# v0.net
KiCad netlist of a schematic drawn in Altium Designer
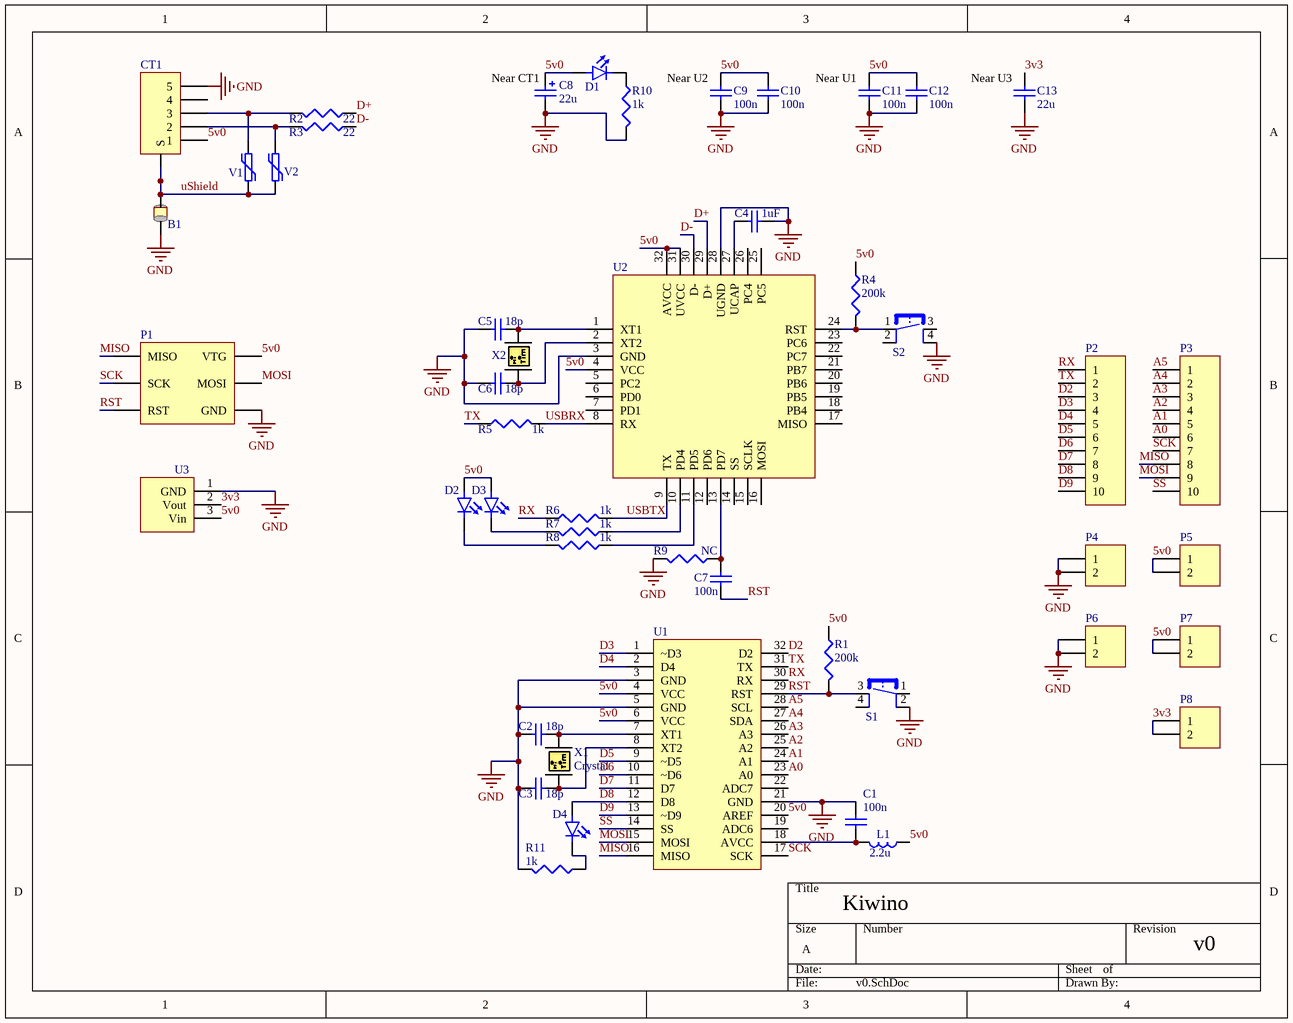
[diagram p0: v0.SchDoc]

(export (version "E")
  (design (tool "Eeschema 10.0.6"))
  (components
    (comp (ref "B1")
      (value "Ferrite Bead")
      (footprint "smd0603")
      (libsource (lib "Components") (part "Ferrite Bead"))
    )
    (comp (ref "C1")
      (value "100n")
      (footprint "SMD0603_cap")
      (description "Ceramic Chip Capacitor")
      (fields (field (name "Comment") "Cap"))
      (libsource (lib "Components") (part "Capacitor Ceramic"))
    )
    (comp (ref "C2")
      (value "18p")
      (footprint "SMD0603_cap")
      (description "Ceramic Chip Capacitor")
      (fields (field (name "Comment") "Cap"))
      (libsource (lib "Components") (part "Capacitor Ceramic"))
    )
    (comp (ref "C3")
      (value "18p")
      (footprint "SMD0603_cap")
      (description "Ceramic Chip Capacitor")
      (fields (field (name "Comment") "Cap"))
      (libsource (lib "Components") (part "Capacitor Ceramic"))
    )
    (comp (ref "C4")
      (value "1uF")
      (footprint "SMD0603_cap")
      (description "Ceramic Chip Capacitor")
      (fields (field (name "Comment") "Cap"))
      (libsource (lib "Components") (part "Capacitor Ceramic"))
    )
    (comp (ref "C5")
      (value "18p")
      (footprint "SMD0603_cap")
      (description "Ceramic Chip Capacitor")
      (fields (field (name "Comment") "Cap"))
      (libsource (lib "Components") (part "Capacitor Ceramic"))
    )
    (comp (ref "C6")
      (value "18p")
      (footprint "SMD0603_cap")
      (description "Ceramic Chip Capacitor")
      (fields (field (name "Comment") "Cap"))
      (libsource (lib "Components") (part "Capacitor Ceramic"))
    )
    (comp (ref "C7")
      (value "100n")
      (footprint "SMD0603_cap")
      (description "Ceramic Chip Capacitor")
      (fields (field (name "Comment") "Cap"))
      (libsource (lib "Components") (part "Capacitor Ceramic"))
    )
    (comp (ref "C8")
      (value "22u")
      (footprint "cap_radial_b")
      (description "Polarized Capacitor (Surface Mount)")
      (fields (field (name "Comment") "Cap"))
      (libsource (lib "Components") (part "Capacitor Polarized"))
    )
    (comp (ref "C9")
      (value "100n")
      (footprint "SMD0603_cap")
      (description "Ceramic Chip Capacitor")
      (fields (field (name "Comment") "Cap"))
      (libsource (lib "Components") (part "Capacitor Ceramic"))
    )
    (comp (ref "C10")
      (value "100n")
      (footprint "SMD0603_cap")
      (description "Ceramic Chip Capacitor")
      (fields (field (name "Comment") "Cap"))
      (libsource (lib "Components") (part "Capacitor Ceramic"))
    )
    (comp (ref "C11")
      (value "100n")
      (footprint "SMD0603_cap")
      (description "Ceramic Chip Capacitor")
      (fields (field (name "Comment") "Cap"))
      (libsource (lib "Components") (part "Capacitor Ceramic"))
    )
    (comp (ref "C12")
      (value "100n")
      (footprint "SMD0603_cap")
      (description "Ceramic Chip Capacitor")
      (fields (field (name "Comment") "Cap"))
      (libsource (lib "Components") (part "Capacitor Ceramic"))
    )
    (comp (ref "C13")
      (value "22u")
      (footprint "SMD0603_cap")
      (description "Ceramic Chip Capacitor")
      (fields (field (name "Comment") "Cap"))
      (libsource (lib "Components") (part "Capacitor Ceramic"))
    )
    (comp (ref "CT1")
      (value "Header")
      (footprint "microusb_2")
      (description "Micro USB")
      (libsource (lib "Components") (part "MICROUSB"))
    )
    (comp (ref "D1")
      (value "LED")
      (footprint "SMD0603 POLARIZED")
      (libsource (lib "Components") (part "LED"))
    )
    (comp (ref "D2")
      (value "LED")
      (footprint "SMD0603 POLARIZED")
      (libsource (lib "Components") (part "LED"))
    )
    (comp (ref "D3")
      (value "LED")
      (footprint "SMD0603 POLARIZED")
      (libsource (lib "Components") (part "LED"))
    )
    (comp (ref "D4")
      (value "LED")
      (footprint "SMD0603 POLARIZED")
      (libsource (lib "Components") (part "LED"))
    )
    (comp (ref "L1")
      (value "2.2u")
      (footprint "SMD0805")
      (description "Inductor")
      (fields (field (name "PUBLISHER") "Altium Limited"))
      (libsource (lib "Components") (part "Inductor"))
    )
    (comp (ref "P1")
      (value "ICSP Header")
      (footprint "Header 2x3")
      (libsource (lib "Components") (part "ICSP Header"))
    )
    (comp (ref "P2")
      (value "Header 10x1")
      (footprint "header 10x1")
      (libsource (lib "Components") (part "Header 10x1"))
    )
    (comp (ref "P3")
      (value "Header 10x1")
      (footprint "header 10x1")
      (libsource (lib "Components") (part "Header 10x1"))
    )
    (comp (ref "P4")
      (value "Header")
      (footprint "Header 2x1")
      (description "Header, 2-Pin")
      (libsource (lib "Components") (part "Header 2x1"))
    )
    (comp (ref "P5")
      (value "Header")
      (footprint "Header 2x1")
      (description "Header, 2-Pin")
      (libsource (lib "Components") (part "Header 2x1"))
    )
    (comp (ref "P6")
      (value "Header")
      (footprint "Header 2x1")
      (description "Header, 2-Pin")
      (libsource (lib "Components") (part "Header 2x1"))
    )
    (comp (ref "P7")
      (value "Header")
      (footprint "Header 2x1")
      (description "Header, 2-Pin")
      (libsource (lib "Components") (part "Header 2x1"))
    )
    (comp (ref "P8")
      (value "Header")
      (footprint "Header 2x1")
      (description "Header, 2-Pin")
      (libsource (lib "Components") (part "Header 2x1"))
    )
    (comp (ref "R1")
      (value "200k")
      (footprint "SMD0603")
      (description "Resistor")
      (fields (field (name "Comment") "Res"))
      (libsource (lib "Components") (part "Resistor"))
    )
    (comp (ref "R2")
      (value "22")
      (footprint "SMD0603")
      (description "Resistor")
      (fields (field (name "Comment") "Res"))
      (libsource (lib "Components") (part "Resistor"))
    )
    (comp (ref "R3")
      (value "22")
      (footprint "SMD0603")
      (description "Resistor")
      (fields (field (name "Comment") "Res"))
      (libsource (lib "Components") (part "Resistor"))
    )
    (comp (ref "R4")
      (value "200k")
      (footprint "SMD0603")
      (description "Resistor")
      (fields (field (name "Comment") "Res"))
      (libsource (lib "Components") (part "Resistor"))
    )
    (comp (ref "R5")
      (value "1k")
      (footprint "SMD0603")
      (description "Resistor")
      (fields (field (name "Comment") "Res"))
      (libsource (lib "Components") (part "Resistor"))
    )
    (comp (ref "R6")
      (value "1k")
      (footprint "SMD0603")
      (description "Resistor")
      (fields (field (name "Comment") "Res"))
      (libsource (lib "Components") (part "Resistor"))
    )
    (comp (ref "R7")
      (value "1k")
      (footprint "SMD0603")
      (description "Resistor")
      (fields (field (name "Comment") "Res"))
      (libsource (lib "Components") (part "Resistor"))
    )
    (comp (ref "R8")
      (value "1k")
      (footprint "SMD0603")
      (description "Resistor")
      (fields (field (name "Comment") "Res"))
      (libsource (lib "Components") (part "Resistor"))
    )
    (comp (ref "R9")
      (value "NC")
      (footprint "SMD0603")
      (description "Resistor")
      (fields (field (name "Comment") "Res"))
      (libsource (lib "Components") (part "Resistor"))
    )
    (comp (ref "R10")
      (value "1k")
      (footprint "SMD0603")
      (description "Resistor")
      (fields (field (name "Comment") "Res"))
      (libsource (lib "Components") (part "Resistor"))
    )
    (comp (ref "R11")
      (value "1k")
      (footprint "SMD0603")
      (description "Resistor")
      (fields (field (name "Comment") "Res"))
      (libsource (lib "Components") (part "Resistor"))
    )
    (comp (ref "S1")
      (value "Pushbutton")
      (footprint "pushbutton_smd")
      (libsource (lib "Components") (part "Pushbutton"))
    )
    (comp (ref "S2")
      (value "Pushbutton")
      (footprint "pushbutton_smd")
      (libsource (lib "Components") (part "Pushbutton"))
    )
    (comp (ref "U1")
      (value "ATMega328P_SMD")
      (footprint "tqfp-32")
      (libsource (lib "Components") (part "ATMega328P_SMD"))
    )
    (comp (ref "U2")
      (value "ATMega16U2")
      (footprint "tqfp-32")
      (libsource (lib "Components") (part "ATMega16U2"))
    )
    (comp (ref "U3")
      (value "AZ1117CH")
      (footprint "sot-223")
      (libsource (lib "Components") (part "AZ1117CH"))
    )
    (comp (ref "V1")
      (value "Varistor")
      (footprint "smd0603")
      (libsource (lib "Components") (part "Varistor"))
    )
    (comp (ref "V2")
      (value "Varistor")
      (footprint "smd0603")
      (libsource (lib "Components") (part "Varistor"))
    )
    (comp (ref "X1")
      (value "Crystal")
      (footprint "crystal_smd_2pin")
      (libsource (lib "Components") (part "Crystal"))
    )
    (comp (ref "X2")
      (value "Crystal")
      (footprint "crystal_smd_2pin")
      (libsource (lib "Components") (part "Crystal"))
    )
  )
  (nets
    (net (code "1") (name "/3v3") (class "Default")
      (node (ref "C13") (pin "1") (pinfunction "1_1") (pintype "passive"))
      (node (ref "P8") (pin "1") (pinfunction "1_1") (pintype "passive"))
      (node (ref "P8") (pin "2") (pinfunction "2_2") (pintype "passive"))
      (node (ref "U3") (pin "2") (pinfunction "Vout_2") (pintype "passive"))
    )
    (net (code "2") (name "/5v0") (class "Default")
      (node (ref "C10") (pin "1") (pinfunction "1_1") (pintype "passive"))
      (node (ref "C11") (pin "1") (pinfunction "1_1") (pintype "passive"))
      (node (ref "C12") (pin "1") (pinfunction "1_1") (pintype "passive"))
      (node (ref "C8") (pin "1") (pinfunction "1_1") (pintype "passive"))
      (node (ref "C9") (pin "1") (pinfunction "1_1") (pintype "passive"))
      (node (ref "CT1") (pin "1") (pinfunction "1_1") (pintype "passive"))
      (node (ref "D1") (pin "1") (pinfunction "Anode_(+)_1") (pintype "passive"))
      (node (ref "D2") (pin "1") (pinfunction "Anode_(+)_1") (pintype "passive"))
      (node (ref "D3") (pin "1") (pinfunction "Anode_(+)_1") (pintype "passive"))
      (node (ref "L1") (pin "1") (pinfunction "Source_1") (pintype "passive"))
      (node (ref "P1") (pin "2") (pinfunction "VTG_2") (pintype "passive"))
      (node (ref "P5") (pin "1") (pinfunction "1_1") (pintype "passive"))
      (node (ref "P5") (pin "2") (pinfunction "2_2") (pintype "passive"))
      (node (ref "P7") (pin "1") (pinfunction "1_1") (pintype "passive"))
      (node (ref "P7") (pin "2") (pinfunction "2_2") (pintype "passive"))
      (node (ref "R1") (pin "2") (pinfunction "2_2") (pintype "passive"))
      (node (ref "R4") (pin "2") (pinfunction "2_2") (pintype "passive"))
      (node (ref "U1") (pin "20") (pinfunction "AREF_20") (pintype "passive"))
      (node (ref "U1") (pin "4") (pinfunction "VCC_4") (pintype "passive"))
      (node (ref "U1") (pin "6") (pinfunction "VCC_6") (pintype "passive"))
      (node (ref "U2") (pin "31") (pinfunction "UVCC_31") (pintype "passive"))
      (node (ref "U2") (pin "32") (pinfunction "AVCC_32") (pintype "passive"))
      (node (ref "U2") (pin "4") (pinfunction "VCC_4") (pintype "passive"))
      (node (ref "U3") (pin "3") (pinfunction "Vin_3") (pintype "passive"))
    )
    (net (code "3") (name "/A0") (class "Default")
      (node (ref "P3") (pin "6") (pinfunction "6_6") (pintype "passive"))
      (node (ref "U1") (pin "23") (pinfunction "A0_23") (pintype "passive"))
    )
    (net (code "4") (name "/A1") (class "Default")
      (node (ref "P3") (pin "5") (pinfunction "5_5") (pintype "passive"))
      (node (ref "U1") (pin "24") (pinfunction "A1_24") (pintype "passive"))
    )
    (net (code "5") (name "/A2") (class "Default")
      (node (ref "P3") (pin "4") (pinfunction "4_4") (pintype "passive"))
      (node (ref "U1") (pin "25") (pinfunction "A2_25") (pintype "passive"))
    )
    (net (code "6") (name "/A3") (class "Default")
      (node (ref "P3") (pin "3") (pinfunction "3_3") (pintype "passive"))
      (node (ref "U1") (pin "26") (pinfunction "A3_26") (pintype "passive"))
    )
    (net (code "7") (name "/A4") (class "Default")
      (node (ref "P3") (pin "2") (pinfunction "2_2") (pintype "passive"))
      (node (ref "U1") (pin "27") (pinfunction "SDA_27") (pintype "passive"))
    )
    (net (code "8") (name "/A5") (class "Default")
      (node (ref "P3") (pin "1") (pinfunction "1_1") (pintype "passive"))
      (node (ref "U1") (pin "28") (pinfunction "SCL_28") (pintype "passive"))
    )
    (net (code "9") (name "/D+") (class "Default")
      (node (ref "R2") (pin "1") (pinfunction "1_1") (pintype "passive"))
      (node (ref "U2") (pin "29") (pinfunction "D+_29") (pintype "passive"))
    )
    (net (code "10") (name "/D-") (class "Default")
      (node (ref "R3") (pin "1") (pinfunction "1_1") (pintype "passive"))
      (node (ref "U2") (pin "30") (pinfunction "D-_30") (pintype "passive"))
    )
    (net (code "11") (name "/D2") (class "Default")
      (node (ref "P2") (pin "3") (pinfunction "3_3") (pintype "passive"))
      (node (ref "U1") (pin "32") (pinfunction "D2_32") (pintype "passive"))
    )
    (net (code "12") (name "/D3") (class "Default")
      (node (ref "P2") (pin "4") (pinfunction "4_4") (pintype "passive"))
      (node (ref "U1") (pin "1") (pinfunction "~D3_1") (pintype "passive"))
    )
    (net (code "13") (name "/D4") (class "Default")
      (node (ref "P2") (pin "5") (pinfunction "5_5") (pintype "passive"))
      (node (ref "U1") (pin "2") (pinfunction "D4_2") (pintype "passive"))
    )
    (net (code "14") (name "/D5") (class "Default")
      (node (ref "P2") (pin "6") (pinfunction "6_6") (pintype "passive"))
      (node (ref "U1") (pin "9") (pinfunction "~D5_9") (pintype "passive"))
    )
    (net (code "15") (name "/D6") (class "Default")
      (node (ref "P2") (pin "7") (pinfunction "7_7") (pintype "passive"))
      (node (ref "U1") (pin "10") (pinfunction "~D6_10") (pintype "passive"))
    )
    (net (code "16") (name "/D7") (class "Default")
      (node (ref "P2") (pin "8") (pinfunction "8_8") (pintype "passive"))
      (node (ref "U1") (pin "11") (pinfunction "D7_11") (pintype "passive"))
    )
    (net (code "17") (name "/D8") (class "Default")
      (node (ref "D4") (pin "1") (pinfunction "Anode_(+)_1") (pintype "passive"))
      (node (ref "P2") (pin "9") (pinfunction "9_9") (pintype "passive"))
      (node (ref "U1") (pin "12") (pinfunction "D8_12") (pintype "passive"))
    )
    (net (code "18") (name "/D9") (class "Default")
      (node (ref "P2") (pin "10") (pinfunction "10_10") (pintype "passive"))
      (node (ref "U1") (pin "13") (pinfunction "~D9_13") (pintype "passive"))
    )
    (net (code "19") (name "/MISO") (class "Default")
      (node (ref "P1") (pin "1") (pinfunction "MISO_1") (pintype "passive"))
      (node (ref "P3") (pin "8") (pinfunction "8_8") (pintype "passive"))
      (node (ref "U1") (pin "16") (pinfunction "MISO_16") (pintype "passive"))
    )
    (net (code "20") (name "/MOSI") (class "Default")
      (node (ref "P1") (pin "4") (pinfunction "MOSI_4") (pintype "passive"))
      (node (ref "P3") (pin "9") (pinfunction "9_9") (pintype "passive"))
      (node (ref "U1") (pin "15") (pinfunction "MOSI_15") (pintype "passive"))
    )
    (net (code "21") (name "/RST") (class "Default")
      (node (ref "C7") (pin "2") (pinfunction "2_2") (pintype "passive"))
      (node (ref "P1") (pin "5") (pinfunction "RST_5") (pintype "passive"))
      (node (ref "R1") (pin "1") (pinfunction "1_1") (pintype "passive"))
      (node (ref "S1") (pin "3") (pintype "passive"))
      (node (ref "U1") (pin "29") (pinfunction "RST_29") (pintype "passive"))
    )
    (net (code "22") (name "/RX") (class "Default")
      (node (ref "P2") (pin "1") (pinfunction "1_1") (pintype "passive"))
      (node (ref "R6") (pin "1") (pinfunction "1_1") (pintype "passive"))
      (node (ref "U1") (pin "30") (pinfunction "RX_30") (pintype "passive"))
    )
    (net (code "23") (name "/SCK") (class "Default")
      (node (ref "P1") (pin "3") (pinfunction "SCK_3") (pintype "passive"))
      (node (ref "P3") (pin "7") (pinfunction "7_7") (pintype "passive"))
      (node (ref "U1") (pin "17") (pinfunction "SCK_17") (pintype "passive"))
    )
    (net (code "24") (name "/SS") (class "Default")
      (node (ref "P3") (pin "10") (pinfunction "10_10") (pintype "passive"))
      (node (ref "U1") (pin "14") (pinfunction "SS_14") (pintype "passive"))
    )
    (net (code "25") (name "/TX") (class "Default")
      (node (ref "P2") (pin "2") (pinfunction "2_2") (pintype "passive"))
      (node (ref "R5") (pin "1") (pinfunction "1_1") (pintype "passive"))
      (node (ref "U1") (pin "31") (pinfunction "TX_31") (pintype "passive"))
    )
    (net (code "26") (name "/USBRX") (class "Default")
      (node (ref "R5") (pin "2") (pinfunction "2_2") (pintype "passive"))
      (node (ref "U2") (pin "8") (pinfunction "RX_8") (pintype "passive"))
    )
    (net (code "27") (name "/USBTX") (class "Default")
      (node (ref "R6") (pin "2") (pinfunction "2_2") (pintype "passive"))
      (node (ref "U2") (pin "9") (pinfunction "TX_9") (pintype "passive"))
    )
    (net (code "28") (name "/uShield") (class "Default")
      (node (ref "B1") (pin "1") (pinfunction "1_1") (pintype "passive"))
      (node (ref "CT1") (pin "S") (pinfunction "S_S") (pintype "passive"))
      (node (ref "V1") (pin "1") (pinfunction "1_1") (pintype "passive"))
      (node (ref "V2") (pin "1") (pinfunction "1_1") (pintype "passive"))
    )
    (net (code "29") (name "GND") (class "Default")
      (node (ref "B1") (pin "2") (pinfunction "2_2") (pintype "passive"))
      (node (ref "C1") (pin "2") (pinfunction "2_2") (pintype "passive"))
      (node (ref "C10") (pin "2") (pinfunction "2_2") (pintype "passive"))
      (node (ref "C11") (pin "2") (pinfunction "2_2") (pintype "passive"))
      (node (ref "C12") (pin "2") (pinfunction "2_2") (pintype "passive"))
      (node (ref "C13") (pin "2") (pinfunction "2_2") (pintype "passive"))
      (node (ref "C2") (pin "2") (pinfunction "2_2") (pintype "passive"))
      (node (ref "C3") (pin "2") (pinfunction "2_2") (pintype "passive"))
      (node (ref "C4") (pin "2") (pinfunction "2_2") (pintype "passive"))
      (node (ref "C5") (pin "2") (pinfunction "2_2") (pintype "passive"))
      (node (ref "C6") (pin "2") (pinfunction "2_2") (pintype "passive"))
      (node (ref "C8") (pin "2") (pinfunction "2_2") (pintype "passive"))
      (node (ref "C9") (pin "2") (pinfunction "2_2") (pintype "passive"))
      (node (ref "CT1") (pin "5") (pinfunction "5_5") (pintype "passive"))
      (node (ref "P1") (pin "6") (pinfunction "GND_6") (pintype "passive"))
      (node (ref "P4") (pin "1") (pinfunction "1_1") (pintype "passive"))
      (node (ref "P4") (pin "2") (pinfunction "2_2") (pintype "passive"))
      (node (ref "P6") (pin "1") (pinfunction "1_1") (pintype "passive"))
      (node (ref "P6") (pin "2") (pinfunction "2_2") (pintype "passive"))
      (node (ref "R10") (pin "2") (pinfunction "2_2") (pintype "passive"))
      (node (ref "R11") (pin "2") (pinfunction "2_2") (pintype "passive"))
      (node (ref "R9") (pin "2") (pinfunction "2_2") (pintype "passive"))
      (node (ref "S1") (pin "2") (pintype "passive"))
      (node (ref "S2") (pin "4") (pintype "passive"))
      (node (ref "U1") (pin "21") (pinfunction "GND_21") (pintype "passive"))
      (node (ref "U1") (pin "3") (pinfunction "GND_3") (pintype "passive"))
      (node (ref "U1") (pin "5") (pinfunction "GND_5") (pintype "passive"))
      (node (ref "U2") (pin "28") (pinfunction "UGND_28") (pintype "passive"))
      (node (ref "U2") (pin "3") (pinfunction "GND_3") (pintype "passive"))
      (node (ref "U3") (pin "1") (pinfunction "GND_1") (pintype "passive"))
    )
    (net (code "30") (name "Net-(CT1-Pad2)") (class "Default")
      (node (ref "CT1") (pin "2") (pinfunction "2_2") (pintype "passive"))
      (node (ref "R3") (pin "2") (pinfunction "2_2") (pintype "passive"))
      (node (ref "V2") (pin "2") (pinfunction "2_2") (pintype "passive"))
    )
    (net (code "31") (name "Net-(CT1-Pad3)") (class "Default")
      (node (ref "CT1") (pin "3") (pinfunction "3_3") (pintype "passive"))
      (node (ref "R2") (pin "2") (pinfunction "2_2") (pintype "passive"))
      (node (ref "V1") (pin "2") (pinfunction "2_2") (pintype "passive"))
    )
    (net (code "32") (name "Net-(D1-Cathode_(-))") (class "Default")
      (node (ref "D1") (pin "2") (pinfunction "Cathode_(-)_2") (pintype "passive"))
      (node (ref "R10") (pin "1") (pinfunction "1_1") (pintype "passive"))
    )
    (net (code "33") (name "Net-(D2-Cathode_(-))") (class "Default")
      (node (ref "D2") (pin "2") (pinfunction "Cathode_(-)_2") (pintype "passive"))
      (node (ref "R8") (pin "2") (pinfunction "2_2") (pintype "passive"))
    )
    (net (code "34") (name "Net-(D3-Cathode_(-))") (class "Default")
      (node (ref "D3") (pin "2") (pinfunction "Cathode_(-)_2") (pintype "passive"))
      (node (ref "R7") (pin "2") (pinfunction "2_2") (pintype "passive"))
    )
    (net (code "35") (name "Net-(D4-Cathode_(-))") (class "Default")
      (node (ref "D4") (pin "2") (pinfunction "Cathode_(-)_2") (pintype "passive"))
      (node (ref "R11") (pin "1") (pinfunction "1_1") (pintype "passive"))
    )
    (net (code "36") (name "Net-(U1-AVCC)") (class "Default")
      (node (ref "C1") (pin "1") (pinfunction "1_1") (pintype "passive"))
      (node (ref "L1") (pin "2") (pinfunction "Source_2") (pintype "passive"))
      (node (ref "U1") (pin "18") (pinfunction "AVCC_18") (pintype "passive"))
    )
    (net (code "37") (name "Net-(U1-XT1)") (class "Default")
      (node (ref "C2") (pin "1") (pinfunction "1_1") (pintype "passive"))
      (node (ref "U1") (pin "7") (pinfunction "XT1_7") (pintype "passive"))
      (node (ref "X1") (pin "2") (pintype "passive"))
    )
    (net (code "38") (name "Net-(U1-XT2)") (class "Default")
      (node (ref "C3") (pin "1") (pinfunction "1_1") (pintype "passive"))
      (node (ref "U1") (pin "8") (pinfunction "XT2_8") (pintype "passive"))
      (node (ref "X1") (pin "1") (pintype "passive"))
    )
    (net (code "39") (name "Net-(U2-PD4)") (class "Default")
      (node (ref "R7") (pin "1") (pinfunction "1_1") (pintype "passive"))
      (node (ref "U2") (pin "10") (pinfunction "PD4_10") (pintype "passive"))
    )
    (net (code "40") (name "Net-(U2-PD5)") (class "Default")
      (node (ref "R8") (pin "1") (pinfunction "1_1") (pintype "passive"))
      (node (ref "U2") (pin "11") (pinfunction "PD5_11") (pintype "passive"))
    )
    (net (code "41") (name "Net-(U2-PD7)") (class "Default")
      (node (ref "C7") (pin "1") (pinfunction "1_1") (pintype "passive"))
      (node (ref "R9") (pin "1") (pinfunction "1_1") (pintype "passive"))
      (node (ref "U2") (pin "13") (pinfunction "PD7_13") (pintype "passive"))
    )
    (net (code "42") (name "Net-(U2-RST)") (class "Default")
      (node (ref "R4") (pin "1") (pinfunction "1_1") (pintype "passive"))
      (node (ref "S2") (pin "1") (pintype "passive"))
      (node (ref "U2") (pin "24") (pinfunction "RST_24") (pintype "passive"))
    )
    (net (code "43") (name "Net-(U2-UCAP)") (class "Default")
      (node (ref "C4") (pin "1") (pinfunction "1_1") (pintype "passive"))
      (node (ref "U2") (pin "27") (pinfunction "UCAP_27") (pintype "passive"))
    )
    (net (code "44") (name "Net-(U2-XT1)") (class "Default")
      (node (ref "C5") (pin "1") (pinfunction "1_1") (pintype "passive"))
      (node (ref "U2") (pin "1") (pinfunction "XT1_1") (pintype "passive"))
      (node (ref "X2") (pin "2") (pintype "passive"))
    )
    (net (code "45") (name "Net-(U2-XT2)") (class "Default")
      (node (ref "C6") (pin "1") (pinfunction "1_1") (pintype "passive"))
      (node (ref "U2") (pin "2") (pinfunction "XT2_2") (pintype "passive"))
      (node (ref "X2") (pin "1") (pintype "passive"))
    )
    (net (code "46") (name "unconnected-(CT1-Pad4)") (class "Default")
      (node (ref "CT1") (pin "4") (pinfunction "4_4") (pintype "passive"))
    )
    (net (code "47") (name "unconnected-(S1-Pad1)") (class "Default")
      (node (ref "S1") (pin "1") (pintype "passive"))
    )
    (net (code "48") (name "unconnected-(S1-Pad4)") (class "Default")
      (node (ref "S1") (pin "4") (pintype "passive"))
    )
    (net (code "49") (name "unconnected-(S2-Pad2)") (class "Default")
      (node (ref "S2") (pin "2") (pintype "passive"))
    )
    (net (code "50") (name "unconnected-(S2-Pad3)") (class "Default")
      (node (ref "S2") (pin "3") (pintype "passive"))
    )
    (net (code "51") (name "unconnected-(U1-ADC6-Pad19)") (class "Default")
      (node (ref "U1") (pin "19") (pinfunction "ADC6_19") (pintype "passive"))
    )
    (net (code "52") (name "unconnected-(U1-ADC7-Pad22)") (class "Default")
      (node (ref "U1") (pin "22") (pinfunction "ADC7_22") (pintype "passive"))
    )
    (net (code "53") (name "unconnected-(U2-MISO-Pad17)") (class "Default")
      (node (ref "U2") (pin "17") (pinfunction "MISO_17") (pintype "passive"))
    )
    (net (code "54") (name "unconnected-(U2-MOSI-Pad16)") (class "Default")
      (node (ref "U2") (pin "16") (pinfunction "MOSI_16") (pintype "passive"))
    )
    (net (code "55") (name "unconnected-(U2-PB4-Pad18)") (class "Default")
      (node (ref "U2") (pin "18") (pinfunction "PB4_18") (pintype "passive"))
    )
    (net (code "56") (name "unconnected-(U2-PB5-Pad19)") (class "Default")
      (node (ref "U2") (pin "19") (pinfunction "PB5_19") (pintype "passive"))
    )
    (net (code "57") (name "unconnected-(U2-PB6-Pad20)") (class "Default")
      (node (ref "U2") (pin "20") (pinfunction "PB6_20") (pintype "passive"))
    )
    (net (code "58") (name "unconnected-(U2-PB7-Pad21)") (class "Default")
      (node (ref "U2") (pin "21") (pinfunction "PB7_21") (pintype "passive"))
    )
    (net (code "59") (name "unconnected-(U2-PC2-Pad5)") (class "Default")
      (node (ref "U2") (pin "5") (pinfunction "PC2_5") (pintype "passive"))
    )
    (net (code "60") (name "unconnected-(U2-PC4-Pad26)") (class "Default")
      (node (ref "U2") (pin "26") (pinfunction "PC4_26") (pintype "passive"))
    )
    (net (code "61") (name "unconnected-(U2-PC5-Pad25)") (class "Default")
      (node (ref "U2") (pin "25") (pinfunction "PC5_25") (pintype "passive"))
    )
    (net (code "62") (name "unconnected-(U2-PC6-Pad23)") (class "Default")
      (node (ref "U2") (pin "23") (pinfunction "PC6_23") (pintype "passive"))
    )
    (net (code "63") (name "unconnected-(U2-PC7-Pad22)") (class "Default")
      (node (ref "U2") (pin "22") (pinfunction "PC7_22") (pintype "passive"))
    )
    (net (code "64") (name "unconnected-(U2-PD0-Pad6)") (class "Default")
      (node (ref "U2") (pin "6") (pinfunction "PD0_6") (pintype "passive"))
    )
    (net (code "65") (name "unconnected-(U2-PD1-Pad7)") (class "Default")
      (node (ref "U2") (pin "7") (pinfunction "PD1_7") (pintype "passive"))
    )
    (net (code "66") (name "unconnected-(U2-PD6-Pad12)") (class "Default")
      (node (ref "U2") (pin "12") (pinfunction "PD6_12") (pintype "passive"))
    )
    (net (code "67") (name "unconnected-(U2-SCLK-Pad15)") (class "Default")
      (node (ref "U2") (pin "15") (pinfunction "SCLK_15") (pintype "passive"))
    )
    (net (code "68") (name "unconnected-(U2-SS-Pad14)") (class "Default")
      (node (ref "U2") (pin "14") (pinfunction "SS_14") (pintype "passive"))
    )
  )
)
